# SAM4N_Xplained_Pro_Crystals.net
KiCad netlist of a schematic drawn in Altium Designer
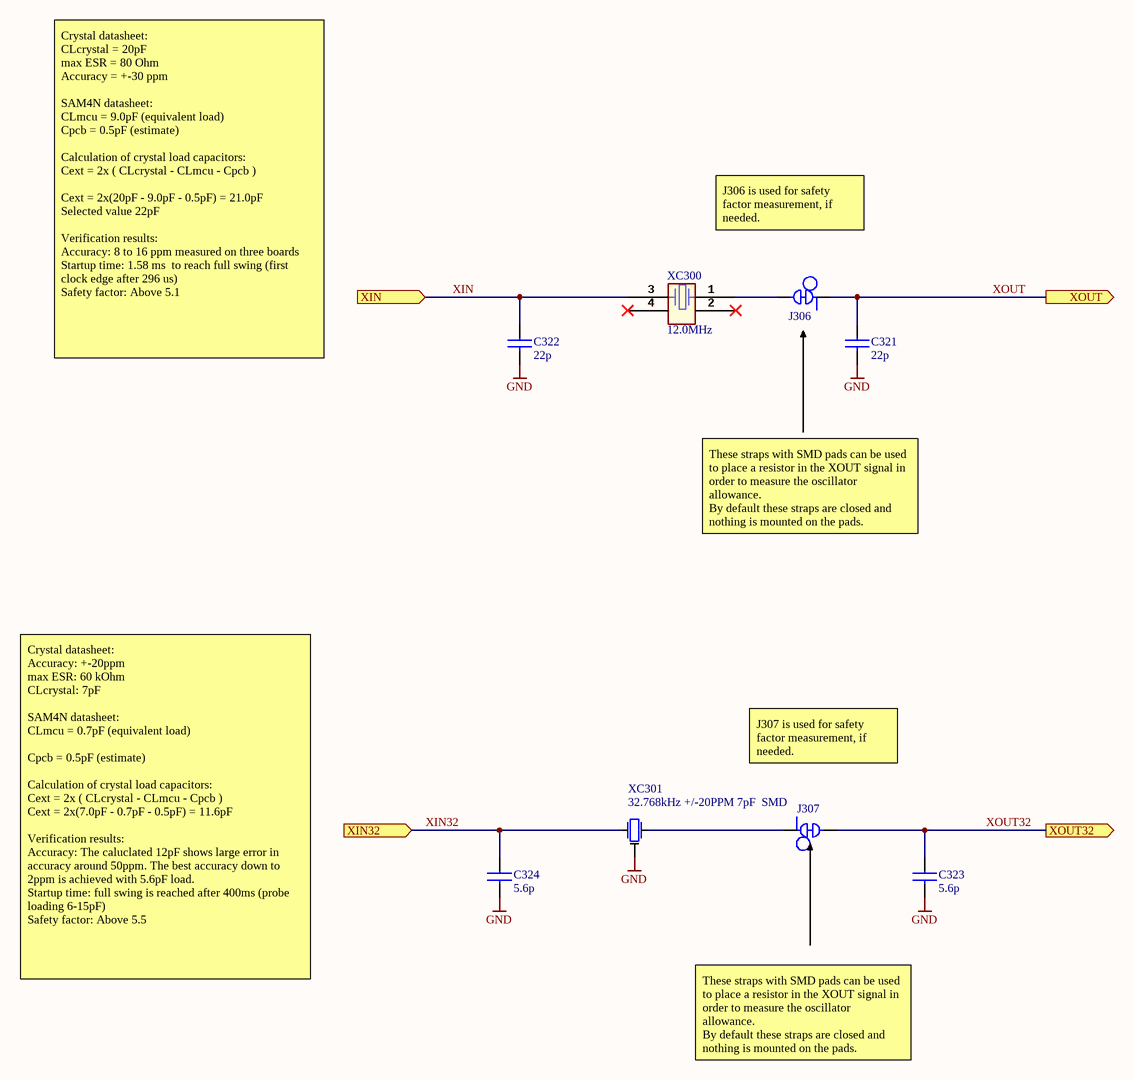
[diagram p0: SAM4N_Xplained_Pro_Crystals.SchDoc]

(export (version "E")
  (design (tool "Eeschema 10.0.6"))
  (components
    (comp (ref "C321")
      (value "22p")
      (footprint "AP1-00001")
      (description "Ceramic capacitor, SMD 0402, NP0, 50V, +/-5%")
      (fields (field (name "TOLERANCE") "50V, +/-5%") (field (name "Comment") "CAP-NONPOL"))
      (libsource (lib "AltiumDbLib") (part "CAP-NONPOL"))
    )
    (comp (ref "C322")
      (value "22p")
      (footprint "AP1-00001")
      (description "Ceramic capacitor, SMD 0402, NP0, 50V, +/-5%")
      (fields (field (name "TOLERANCE") "50V, +/-5%") (field (name "Comment") "CAP-NONPOL"))
      (libsource (lib "AltiumDbLib") (part "CAP-NONPOL"))
    )
    (comp (ref "C323")
      (value "5.6p")
      (footprint "AP1-00001")
      (description "Ceramic capacitor, SMD 0402, NP0, 50V, +/-5%")
      (fields (field (name "TOLERANCE") "50V, +/-5%") (field (name "Comment") "CAP-NONPOL"))
      (libsource (lib "AltiumDbLib") (part "CAP-NONPOL"))
    )
    (comp (ref "C324")
      (value "5.6p")
      (footprint "AP1-00001")
      (description "Ceramic capacitor, SMD 0402, NP0, 50V, +/-5%")
      (fields (field (name "TOLERANCE") "50V, +/-5%") (field (name "Comment") "CAP-NONPOL"))
      (libsource (lib "AltiumDbLib") (part "CAP-NONPOL"))
    )
    (comp (ref "J306")
      (value "SMD-STRAP_CLOSED")
      (footprint "AP9-00044")
      (description "Default closed SMD strap, 0603 size")
      (libsource (lib "AltiumDbLib") (part "SMD-STRAP_CLOSED"))
    )
    (comp (ref "J307")
      (value "SMD-STRAP_CLOSED")
      (footprint "AP9-00044")
      (description "Default closed SMD strap, 0603 size")
      (libsource (lib "AltiumDbLib") (part "SMD-STRAP_CLOSED"))
    )
    (comp (ref "XC300")
      (value "12.0MHz")
      (footprint "AP7-00039")
      (description "Fox FQ5032B 12.0MHz SMD crystal 738B-12")
      (fields (field (name "TOLERANCE") "30PPM") (field (name "MANUFACTURER") "Fox  Electronics"))
      (libsource (lib "AltiumDbLib") (part "CRYSTAL1324"))
    )
    (comp (ref "XC301")
      (value "32.768kHz +/-20PPM 7pF  SMD")
      (footprint "AP7-00044")
      (description "32k768 crystal, +-20ppm, CL=7pF, max ESR 60kOhm, SMD")
      (fields (field (name "TOLERANCE") "+/- 20 PPM") (field (name "MANUFACTURER") "Micro Crystal"))
      (libsource (lib "AltiumDbLib") (part "CRYSTAL_2P_metal"))
    )
  )
  (nets
    (net (code "1") (name "/XIN") (class "Default")
      (node (ref "C322") (pin "1") (pinfunction "1_1") (pintype "passive"))
      (node (ref "XC300") (pin "3") (pinfunction "3_3") (pintype "passive"))
    )
    (net (code "2") (name "/XIN32") (class "Default")
      (node (ref "C324") (pin "1") (pinfunction "1_1") (pintype "passive"))
      (node (ref "XC301") (pin "2") (pinfunction "2_2") (pintype "passive"))
    )
    (net (code "3") (name "/XOUT") (class "Default")
      (node (ref "C321") (pin "1") (pinfunction "1_1") (pintype "passive"))
      (node (ref "J306") (pin "1") (pinfunction "1_1") (pintype "passive"))
    )
    (net (code "4") (name "/XOUT32") (class "Default")
      (node (ref "C323") (pin "1") (pinfunction "1_1") (pintype "passive"))
      (node (ref "J307") (pin "2") (pinfunction "2_2") (pintype "passive"))
    )
    (net (code "5") (name "GND") (class "Default")
      (node (ref "C321") (pin "2") (pinfunction "2_2") (pintype "passive"))
      (node (ref "C322") (pin "2") (pinfunction "2_2") (pintype "passive"))
      (node (ref "C323") (pin "2") (pinfunction "2_2") (pintype "passive"))
      (node (ref "C324") (pin "2") (pinfunction "2_2") (pintype "passive"))
      (node (ref "XC301") (pin "3") (pinfunction "3_3") (pintype "passive"))
    )
    (net (code "6") (name "Net-(J306-Pad2)") (class "Default")
      (node (ref "J306") (pin "2") (pinfunction "2_2") (pintype "passive"))
      (node (ref "XC300") (pin "1") (pinfunction "1_1") (pintype "passive"))
    )
    (net (code "7") (name "Net-(J307-Pad1)") (class "Default")
      (node (ref "J307") (pin "1") (pinfunction "1_1") (pintype "passive"))
      (node (ref "XC301") (pin "1") (pinfunction "1_1") (pintype "passive"))
    )
    (net (code "8") (name "unconnected-(XC300-Pad2)") (class "Default")
      (node (ref "XC300") (pin "2") (pinfunction "2_2") (pintype "passive+no_connect"))
    )
    (net (code "9") (name "unconnected-(XC300-Pad4)") (class "Default")
      (node (ref "XC300") (pin "4") (pinfunction "4_4") (pintype "passive+no_connect"))
    )
  )
)
